# GamePad-PadPCB_v01.net
KiCad netlist of a schematic drawn in EAGLE
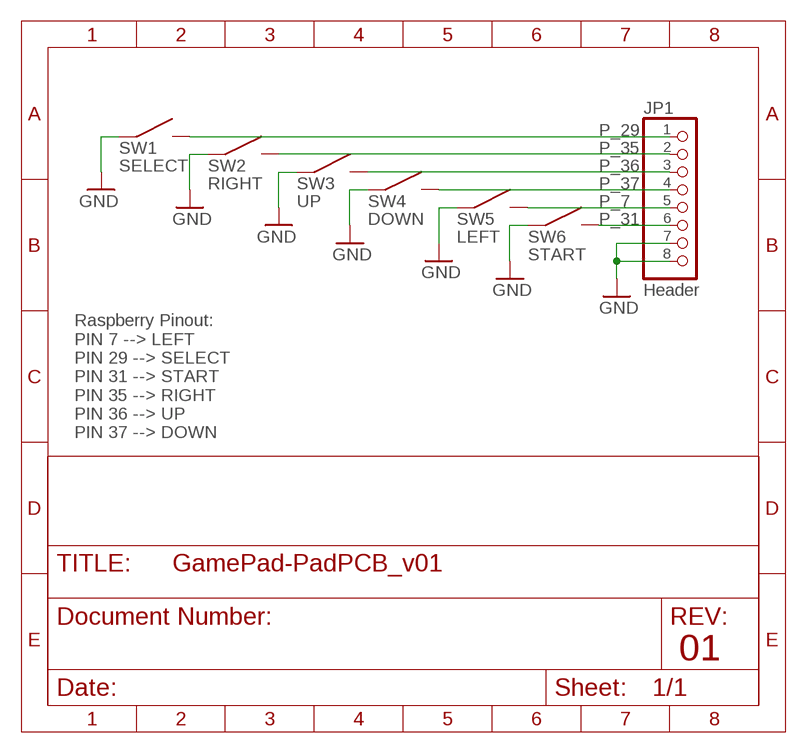
[diagram p0: schematic, sheet 1]

(export (version "E")
  (design (tool "Eeschema 10.0.6"))
  (components
    (comp (ref "JP1")
      (value "Header")
      (footprint "eagle-import:1X08")
      (libsource (lib "eagle-import") (part "PINHD-1X8"))
    )
    (comp (ref "SW1")
      (value "SELECT")
      (footprint "eagle-import:EVPA")
      (libsource (lib "eagle-import") (part "EVPAS"))
    )
    (comp (ref "SW2")
      (value "RIGHT")
      (footprint "eagle-import:EVPA")
      (libsource (lib "eagle-import") (part "EVPAS"))
    )
    (comp (ref "SW3")
      (value "UP")
      (footprint "eagle-import:EVPA")
      (libsource (lib "eagle-import") (part "EVPAS"))
    )
    (comp (ref "SW4")
      (value "DOWN")
      (footprint "eagle-import:EVPA")
      (libsource (lib "eagle-import") (part "EVPAS"))
    )
    (comp (ref "SW5")
      (value "LEFT")
      (footprint "eagle-import:EVPA")
      (libsource (lib "eagle-import") (part "EVPAS"))
    )
    (comp (ref "SW6")
      (value "START")
      (footprint "eagle-import:EVPA")
      (libsource (lib "eagle-import") (part "EVPAS"))
    )
  )
  (nets
    (net (code "1") (name "/P_7") (class "Default")
      (node (ref "JP1") (pin "5") (pinfunction "5_5") (pintype "passive"))
      (node (ref "SW5") (pin "2") (pinfunction "P$2_2") (pintype "bidirectional"))
    )
    (net (code "2") (name "/P_29") (class "Default")
      (node (ref "JP1") (pin "1") (pinfunction "1_1") (pintype "passive"))
      (node (ref "SW1") (pin "2") (pinfunction "P$2_2") (pintype "bidirectional"))
    )
    (net (code "3") (name "/P_31") (class "Default")
      (node (ref "JP1") (pin "6") (pinfunction "6_6") (pintype "passive"))
      (node (ref "SW6") (pin "2") (pinfunction "P$2_2") (pintype "bidirectional"))
    )
    (net (code "4") (name "/P_35") (class "Default")
      (node (ref "JP1") (pin "2") (pinfunction "2_2") (pintype "passive"))
      (node (ref "SW2") (pin "2") (pinfunction "P$2_2") (pintype "bidirectional"))
    )
    (net (code "5") (name "/P_36") (class "Default")
      (node (ref "JP1") (pin "3") (pinfunction "3_3") (pintype "passive"))
      (node (ref "SW3") (pin "2") (pinfunction "P$2_2") (pintype "bidirectional"))
    )
    (net (code "6") (name "/P_37") (class "Default")
      (node (ref "JP1") (pin "4") (pinfunction "4_4") (pintype "passive"))
      (node (ref "SW4") (pin "2") (pinfunction "P$2_2") (pintype "bidirectional"))
    )
    (net (code "7") (name "GND") (class "Default")
      (node (ref "JP1") (pin "7") (pinfunction "7_7") (pintype "passive"))
      (node (ref "JP1") (pin "8") (pinfunction "8_8") (pintype "passive"))
      (node (ref "SW1") (pin "1") (pinfunction "P$1_1") (pintype "bidirectional"))
      (node (ref "SW2") (pin "1") (pinfunction "P$1_1") (pintype "bidirectional"))
      (node (ref "SW3") (pin "1") (pinfunction "P$1_1") (pintype "bidirectional"))
      (node (ref "SW4") (pin "1") (pinfunction "P$1_1") (pintype "bidirectional"))
      (node (ref "SW5") (pin "1") (pinfunction "P$1_1") (pintype "bidirectional"))
      (node (ref "SW6") (pin "1") (pinfunction "P$1_1") (pintype "bidirectional"))
    )
  )
)
